# MCU_MKL05_QFN24.net
KiCad netlist of a schematic drawn in Altium Designer
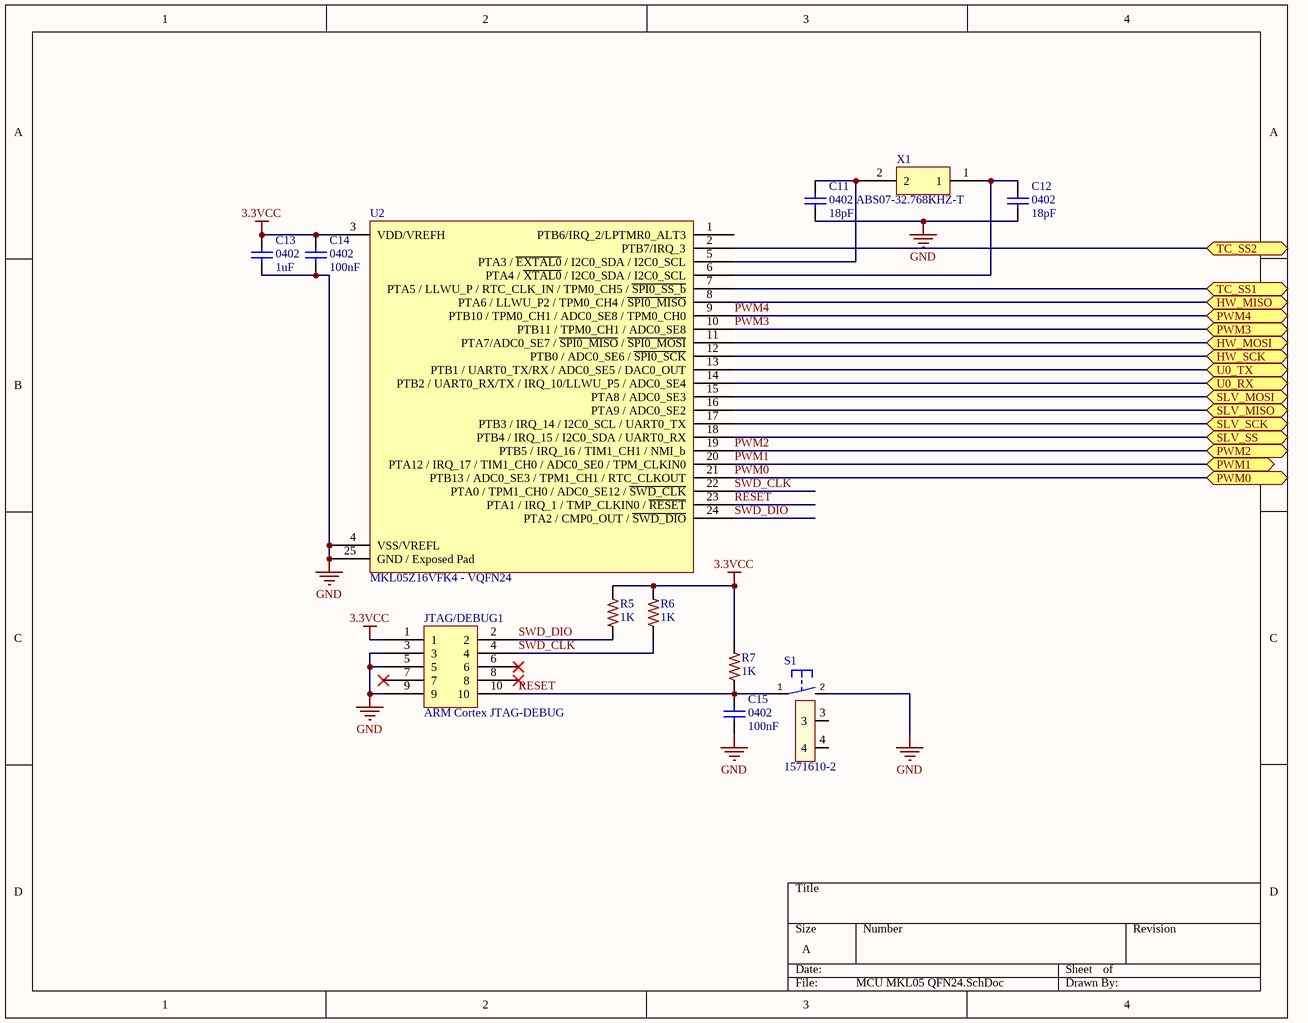
[diagram p0: MCU MKL05 QFN24.SchDoc]

(export (version "E")
  (design (tool "Eeschema 10.0.6"))
  (components
    (comp (ref "C11")
      (value "18pF")
      (footprint "C0402")
      (description "CAP CER 18PF 50V 2% NP0 0402")
      (fields
        (field (name "MANUFACTURE PART #") "CL05C180GB5NNNC")
        (field (name "MANUFACTURER") "Samsung")
        (field (name "PACKAGEREFERENCE") "0402")
        (field (name "PUBLISHER") "Ultimachine")
      )
      (libsource (lib "Tigershark3D") (part "CL05C180GB5NNNC"))
    )
    (comp (ref "C12")
      (value "18pF")
      (footprint "C0402")
      (description "CAP CER 18PF 50V 2% NP0 0402")
      (fields
        (field (name "MANUFACTURE PART #") "CL05C180GB5NNNC")
        (field (name "MANUFACTURER") "Samsung")
        (field (name "PACKAGEREFERENCE") "0402")
        (field (name "PUBLISHER") "Ultimachine")
      )
      (libsource (lib "Tigershark3D") (part "CL05C180GB5NNNC"))
    )
    (comp (ref "C13")
      (value "1uF")
      (footprint "C0402")
      (description "CAP CER 1UF 6.3V 10% X5R 0402")
      (fields
        (field (name "MFR PART #") "GRM155R60J105KE19D")
        (field (name "MFR") "Murata")
        (field (name "PACKAGEREFERENCE") "0402")
        (field (name "PUBLISHER") "Ultimachine")
      )
      (libsource (lib "Tigershark3D") (part "GRM155R60J105KE19D"))
    )
    (comp (ref "C14")
      (value "100nF")
      (footprint "C0402")
      (description "CAP CER 0.1UF (100nF) 16V 10% X7R 0402")
      (fields
        (field (name "MFR PART #") "GRM155R71C104KA88D")
        (field (name "MFR") "Murata")
        (field (name "PACKAGEREFERENCE") "0402")
        (field (name "PUBLISHER") "Ultimachine")
      )
      (libsource (lib "Tigershark3D") (part "GRM155R71C104KA88D"))
    )
    (comp (ref "C15")
      (value "100nF")
      (footprint "C0402")
      (description "CAP CER 0.1UF (100nF) 16V 10% X7R 0402")
      (fields
        (field (name "MFR PART #") "GRM155R71C104KA88D")
        (field (name "MFR") "Murata")
        (field (name "PACKAGEREFERENCE") "0402")
        (field (name "PUBLISHER") "Ultimachine")
      )
      (libsource (lib "Tigershark3D") (part "GRM155R71C104KA88D"))
    )
    (comp (ref "JTAG/DEBUG1")
      (value "ARM Cortex JTAG-DEBUG")
      (footprint "FTSH-105-XX-X-DV")
      (libsource (lib "Adams Altium Library") (part "ARM Cortex JTAG-DEBUG Header"))
    )
    (comp (ref "R5")
      (value "1K")
      (footprint "R0603")
      (description "RES 0603 1K 100mW 1%")
      (fields
        (field (name "MANUFACTURERPARTNUMBER") "ERJ-3EKF1001V")
        (field (name "PUBLISHER") "UltiMachine")
      )
      (libsource (lib "Tigershark3D") (part "ERJ-3EKF1001V"))
    )
    (comp (ref "R6")
      (value "1K")
      (footprint "R0603")
      (description "RES 0603 1K 100mW 1%")
      (fields
        (field (name "MANUFACTURERPARTNUMBER") "ERJ-3EKF1001V")
        (field (name "PUBLISHER") "UltiMachine")
      )
      (libsource (lib "Tigershark3D") (part "ERJ-3EKF1001V"))
    )
    (comp (ref "R7")
      (value "1K")
      (footprint "R0603")
      (description "RES 0603 1K 100mW 1%")
      (fields
        (field (name "MANUFACTURERPARTNUMBER") "ERJ-3EKF1001V")
        (field (name "PUBLISHER") "UltiMachine")
      )
      (libsource (lib "Tigershark3D") (part "ERJ-3EKF1001V"))
    )
    (comp (ref "S1")
      (value "1571610-2")
      (footprint "B3F-31XX")
      (description "SWTCH Momentary Washable")
      (fields
        (field (name "MANUFACTURER") "Omron")
        (field (name "MANUFACTURER_1") "TE")
        (field (name "PUBLISHER") "UltiMachine")
      )
      (libsource (lib "ZMBo Schematic Library") (part "1571610-2_1"))
    )
    (comp (ref "U2")
      (value "MKL05Z16VFK4 - VQFN24")
      (footprint "98ASA00474D")
      (description "ARM Cortex M0+")
      (libsource (lib "SharkPup") (part "MKL05Z16VFK4 - 24 Pin VQFN"))
    )
    (comp (ref "X1")
      (value "ABS07-32.768KHZ-T")
      (footprint "ABS07-32.768KHZ-T")
      (description "ABS07-32.768KHZ-T RTC Crystal Oscillator")
      (libsource (lib "Adams Altium Library") (part "ABS07-32.768KHZ-T"))
    )
  )
  (nets
    (net (code "1") (name "/HW_MISO") (class "Default")
      (node (ref "U2") (pin "8") (pinfunction "PTA6_/_LLWU_P2_/_TPM0_CH4_/_~{SPI0_MISO}_8") (pintype "passive"))
    )
    (net (code "2") (name "/HW_MOSI") (class "Default")
      (node (ref "U2") (pin "11") (pinfunction "PTA7/ADC0_SE7_/_~{SPI0_MISO}_/_~{SPI0_MOSI}_11") (pintype "passive"))
    )
    (net (code "3") (name "/HW_SCK") (class "Default")
      (node (ref "U2") (pin "12") (pinfunction "PTB0_/_ADC0_SE6_/_~{SPI0_SCK}_12") (pintype "passive"))
    )
    (net (code "4") (name "/PWM0") (class "Default")
      (node (ref "U2") (pin "21") (pinfunction "PTB13_/_ADC0_SE3_/_TPM1_CH1_/_RTC_CLKOUT_21") (pintype "passive"))
    )
    (net (code "5") (name "/PWM1") (class "Default")
      (node (ref "U2") (pin "20") (pinfunction "PTA12_/_IRQ_17_/_TIM1_CH0_/_ADC0_SE0_/_TPM_CLKIN0_20") (pintype "passive"))
    )
    (net (code "6") (name "/PWM2") (class "Default")
      (node (ref "U2") (pin "19") (pinfunction "PTB5_/_IRQ_16_/_TIM1_CH1_/_NMI_b_19") (pintype "passive"))
    )
    (net (code "7") (name "/PWM3") (class "Default")
      (node (ref "U2") (pin "10") (pinfunction "PTB11_/_TPM0_CH1_/_ADC0_SE8_10") (pintype "passive"))
    )
    (net (code "8") (name "/PWM4") (class "Default")
      (node (ref "U2") (pin "9") (pinfunction "PTB10_/_TPM0_CH1_/_ADC0_SE8_/_TPM0_CH0_9") (pintype "passive"))
    )
    (net (code "9") (name "/RESET") (class "Default")
      (node (ref "C15") (pin "2") (pinfunction "2_2") (pintype "passive"))
      (node (ref "JTAG/DEBUG1") (pin "10") (pinfunction "10_10") (pintype "passive"))
      (node (ref "R7") (pin "1") (pinfunction "1_1") (pintype "passive"))
      (node (ref "S1") (pin "1") (pinfunction "P_1") (pintype "passive"))
      (node (ref "U2") (pin "23") (pinfunction "PTA1_/_IRQ_1_/_TMP_CLKIN0_/_~{RESET}_23") (pintype "passive"))
    )
    (net (code "10") (name "/SLV_MISO") (class "Default")
      (node (ref "U2") (pin "16") (pinfunction "PTA9_/_ADC0_SE2_16") (pintype "passive"))
    )
    (net (code "11") (name "/SLV_MOSI") (class "Default")
      (node (ref "U2") (pin "15") (pinfunction "PTA8_/_ADC0_SE3_15") (pintype "passive"))
    )
    (net (code "12") (name "/SLV_SCK") (class "Default")
      (node (ref "U2") (pin "17") (pinfunction "PTB3_/_IRQ_14_/_I2C0_SCL_/_UART0_TX_17") (pintype "passive"))
    )
    (net (code "13") (name "/SLV_SS") (class "Default")
      (node (ref "U2") (pin "18") (pinfunction "PTB4_/_IRQ_15_/_I2C0_SDA_/_UART0_RX_18") (pintype "passive"))
    )
    (net (code "14") (name "/SWD_CLK") (class "Default")
      (node (ref "JTAG/DEBUG1") (pin "4") (pinfunction "4_4") (pintype "passive"))
      (node (ref "R6") (pin "1") (pinfunction "1_1") (pintype "passive"))
      (node (ref "U2") (pin "22") (pinfunction "PTA0_/_TPM1_CH0_/_ADC0_SE12_/_~{SWD_CLK}_22") (pintype "passive"))
    )
    (net (code "15") (name "/SWD_DIO") (class "Default")
      (node (ref "JTAG/DEBUG1") (pin "2") (pinfunction "2_2") (pintype "passive"))
      (node (ref "R5") (pin "2") (pinfunction "2_2") (pintype "passive"))
      (node (ref "U2") (pin "24") (pinfunction "PTA2_/_CMP0_OUT_/_~{SWD_DIO}_24") (pintype "passive"))
    )
    (net (code "16") (name "/TC_SS1") (class "Default")
      (node (ref "U2") (pin "7") (pinfunction "PTA5_/_LLWU_P_/_RTC_CLK_IN_/_TPM0_CH5_/_~{SPI0_SS_b}_7") (pintype "passive"))
    )
    (net (code "17") (name "/TC_SS2") (class "Default")
      (node (ref "U2") (pin "2") (pinfunction "PTB7/IRQ_3_2") (pintype "passive"))
    )
    (net (code "18") (name "/U0_RX") (class "Default")
      (node (ref "U2") (pin "14") (pinfunction "PTB2_/_UART0_RX/TX_/_IRQ_10/LLWU_P5_/_ADC0_SE4_14") (pintype "passive"))
    )
    (net (code "19") (name "/U0_TX") (class "Default")
      (node (ref "U2") (pin "13") (pinfunction "PTB1_/_UART0_TX/RX_/_ADC0_SE5_/_DAC0_OUT_13") (pintype "passive"))
    )
    (net (code "20") (name "3.3VCC") (class "Default")
      (node (ref "C13") (pin "2") (pinfunction "2_2") (pintype "passive"))
      (node (ref "C14") (pin "2") (pinfunction "2_2") (pintype "passive"))
      (node (ref "JTAG/DEBUG1") (pin "1") (pinfunction "1_1") (pintype "passive"))
      (node (ref "R5") (pin "1") (pinfunction "1_1") (pintype "passive"))
      (node (ref "R6") (pin "2") (pinfunction "2_2") (pintype "passive"))
      (node (ref "R7") (pin "2") (pinfunction "2_2") (pintype "passive"))
      (node (ref "U2") (pin "3") (pinfunction "VDD/VREFH_3") (pintype "passive"))
    )
    (net (code "21") (name "GND") (class "Default")
      (node (ref "C11") (pin "1") (pinfunction "1_1") (pintype "passive"))
      (node (ref "C12") (pin "1") (pinfunction "1_1") (pintype "passive"))
      (node (ref "C13") (pin "1") (pinfunction "1_1") (pintype "passive"))
      (node (ref "C14") (pin "1") (pinfunction "1_1") (pintype "passive"))
      (node (ref "C15") (pin "1") (pinfunction "1_1") (pintype "passive"))
      (node (ref "JTAG/DEBUG1") (pin "3") (pinfunction "3_3") (pintype "passive"))
      (node (ref "JTAG/DEBUG1") (pin "5") (pinfunction "5_5") (pintype "passive"))
      (node (ref "JTAG/DEBUG1") (pin "9") (pinfunction "9_9") (pintype "passive"))
      (node (ref "S1") (pin "2") (pinfunction "S_2") (pintype "passive"))
      (node (ref "U2") (pin "25") (pinfunction "GND_/_Exposed_Pad_25") (pintype "passive"))
      (node (ref "U2") (pin "4") (pinfunction "VSS/VREFL_4") (pintype "passive"))
    )
    (net (code "22") (name "Net-(U2-PTA3_{slash}_~{EXTAL0}_{slash}_I2C0_SDA_{slash}_I2C0_SCL)") (class "Default")
      (node (ref "C11") (pin "2") (pinfunction "2_2") (pintype "passive"))
      (node (ref "U2") (pin "5") (pinfunction "PTA3_/_~{EXTAL0}_/_I2C0_SDA_/_I2C0_SCL_5") (pintype "passive"))
      (node (ref "X1") (pin "2") (pinfunction "2_2") (pintype "passive"))
    )
    (net (code "23") (name "Net-(U2-PTA4_{slash}_~{XTAL0}_{slash}_I2C0_SDA_{slash}_I2C0_SCL)") (class "Default")
      (node (ref "C12") (pin "2") (pinfunction "2_2") (pintype "passive"))
      (node (ref "U2") (pin "6") (pinfunction "PTA4_/_~{XTAL0}_/_I2C0_SDA_/_I2C0_SCL_6") (pintype "passive"))
      (node (ref "X1") (pin "1") (pinfunction "1_1") (pintype "passive"))
    )
    (net (code "24") (name "unconnected-(JTAG/DEBUG1-Pad6)") (class "Default")
      (node (ref "JTAG/DEBUG1") (pin "6") (pinfunction "6_6") (pintype "passive+no_connect"))
    )
    (net (code "25") (name "unconnected-(JTAG/DEBUG1-Pad7)") (class "Default")
      (node (ref "JTAG/DEBUG1") (pin "7") (pinfunction "7_7") (pintype "passive+no_connect"))
    )
    (net (code "26") (name "unconnected-(JTAG/DEBUG1-Pad8)") (class "Default")
      (node (ref "JTAG/DEBUG1") (pin "8") (pinfunction "8_8") (pintype "passive+no_connect"))
    )
    (net (code "27") (name "unconnected-(S1-Pad3)") (class "Default")
      (node (ref "S1") (pin "3") (pinfunction "3_3") (pintype "power_in"))
    )
    (net (code "28") (name "unconnected-(S1-Pad4)") (class "Default")
      (node (ref "S1") (pin "4") (pinfunction "4_4") (pintype "power_in"))
    )
    (net (code "29") (name "unconnected-(U2-PTB6{slash}IRQ_2{slash}LPTMR0_ALT3-Pad1)") (class "Default")
      (node (ref "U2") (pin "1") (pinfunction "PTB6/IRQ_2/LPTMR0_ALT3_1") (pintype "passive"))
    )
  )
)
